# 02_Connectors.net
KiCad netlist of a schematic drawn in Altium Designer
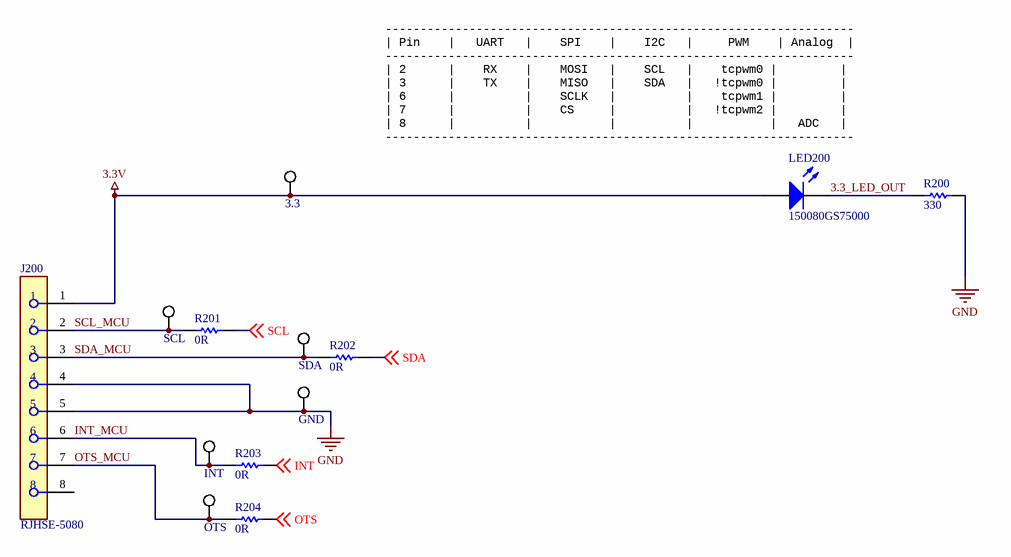
[diagram p0: 02_Connectors.SchDoc]

(export (version "E")
  (design (tool "Eeschema 10.0.6"))
  (components
    (comp (ref "3.3")
      (value "5019")
      (footprint "KSTN-5019_V")
      (description "Test Point, 1 Position SMD, RoHS, Tape and Reel")
      (fields (field (name "MANUFACTURER") "Keystone Electronics"))
      (libsource (lib "ECE453") (part "CMP-1672-00008-1"))
    )
    (comp (ref "GND")
      (value "5019")
      (footprint "KSTN-5019_V")
      (description "Test Point, 1 Position SMD, RoHS, Tape and Reel")
      (fields (field (name "MANUFACTURER") "Keystone Electronics"))
      (libsource (lib "ECE453") (part "CMP-1672-00008-1"))
    )
    (comp (ref "INT")
      (value "5019")
      (footprint "KSTN-5019_V")
      (description "Test Point, 1 Position SMD, RoHS, Tape and Reel")
      (fields (field (name "MANUFACTURER") "Keystone Electronics"))
      (libsource (lib "ECE453") (part "CMP-1672-00008-1"))
    )
    (comp (ref "J200")
      (value "RJHSE-5080")
      (footprint "FP-RJHSE-5080-MFG")
      (description "CONN MOD JACK 8P8C R/A UNSHLD")
      (fields
        (field (name "OCTOPART") "https://octopart.com/rjhse-5080-amphenol-45060")
        (field (name "MANUFACTURER") "Amphenol")
      )
      (libsource (lib "Altium Content Vault") (part "b0a0b555dd3abf3683e7c330df25cc4"))
    )
    (comp (ref "LED200")
      (value "150080GS75000")
      (footprint "0805_A")
      (description "SMD mono-color Chip LED, WL-SMCW, Green")
      (fields (field (name "MANUFACTURER") "Wuerth Elektronik"))
      (libsource (lib "ECE453") (part "CMP-1426-00007-1"))
    )
    (comp (ref "OTS")
      (value "5019")
      (footprint "KSTN-5019_V")
      (description "Test Point, 1 Position SMD, RoHS, Tape and Reel")
      (fields (field (name "MANUFACTURER") "Keystone Electronics"))
      (libsource (lib "ECE453") (part "CMP-1672-00008-1"))
    )
    (comp (ref "R200")
      (value "RC0805FR-07330RL")
      (footprint "RESC2013X60X35LL10T20")
      (description "Chip Resistor, 330 Ohm, +/- 1%, 125 mW, -55 to 155 degC, 0805 (2012 Metric), RoHS, Tape and Reel")
      (fields
        (field (name "MANUFACTURER") "Yageo")
        (field (name "TOLERANCE") "1%")
        (field (name "RESISTANCE") "330")
      )
      (libsource (lib "ECE453") (part "CMP-2000-06960-1"))
    )
    (comp (ref "R201")
      (value "0R")
      (footprint "RES_0805")
      (description "Chip Resistor, 0 Ohm, +/- 1%, 0.125 W, -55 to 155 degC, 0805 (2012 Metric), RoHS, Tape and Reel")
      (fields (field (name "PARTNUMBER") "ERJ-6GEY0R00V") (field (name "TOLERANCE") "5%"))
      (libsource (lib "ECE453") (part "CMP-1665-00002-5"))
    )
    (comp (ref "R202")
      (value "0R")
      (footprint "RESC2013X70X40NL20T20")
      (description "Chip Resistor, 0 Ohm, +/- 1%, 0.125 W, -55 to 155 degC, 0805 (2012 Metric), RoHS, Tape and Reel")
      (fields (field (name "PARTNUMBER") "ERJ-6GEY0R00V") (field (name "TOLERANCE") "5%"))
      (libsource (lib "ECE453") (part "CMP-1665-00002-5"))
    )
    (comp (ref "R203")
      (value "0R")
      (footprint "RESC2013X70X40NL20T20")
      (description "Chip Resistor, 0 Ohm, +/- 1%, 0.125 W, -55 to 155 degC, 0805 (2012 Metric), RoHS, Tape and Reel")
      (fields (field (name "PARTNUMBER") "ERJ-6GEY0R00V") (field (name "TOLERANCE") "5%"))
      (libsource (lib "ECE453") (part "CMP-1665-00002-5"))
    )
    (comp (ref "R204")
      (value "0R")
      (footprint "RESC2013X70X40NL20T20")
      (description "Chip Resistor, 0 Ohm, +/- 1%, 0.125 W, -55 to 155 degC, 0805 (2012 Metric), RoHS, Tape and Reel")
      (fields (field (name "PARTNUMBER") "ERJ-6GEY0R00V") (field (name "TOLERANCE") "5%"))
      (libsource (lib "ECE453") (part "CMP-1665-00002-5"))
    )
    (comp (ref "SCL")
      (value "5019")
      (footprint "KSTN-5019_V")
      (description "Test Point, 1 Position SMD, RoHS, Tape and Reel")
      (fields (field (name "MANUFACTURER") "Keystone Electronics"))
      (libsource (lib "ECE453") (part "CMP-1672-00008-1"))
    )
    (comp (ref "SDA")
      (value "5019")
      (footprint "KSTN-5019_V")
      (description "Test Point, 1 Position SMD, RoHS, Tape and Reel")
      (fields (field (name "MANUFACTURER") "Keystone Electronics"))
      (libsource (lib "ECE453") (part "CMP-1672-00008-1"))
    )
  )
  (nets
    (net (code "1") (name "/3.3_LED_OUT") (class "Default")
      (node (ref "LED200") (pin "1") (pinfunction "K_1") (pintype "passive"))
      (node (ref "R200") (pin "1") (pinfunction "1_1") (pintype "passive"))
    )
    (net (code "2") (name "/INT_MCU") (class "Default")
      (node (ref "INT") (pin "1") (pinfunction "1_1") (pintype "passive"))
      (node (ref "J200") (pin "6") (pinfunction "6_6") (pintype "passive"))
      (node (ref "R203") (pin "1") (pinfunction "1_1") (pintype "passive"))
    )
    (net (code "3") (name "/OTS_MCU") (class "Default")
      (node (ref "J200") (pin "7") (pinfunction "7_7") (pintype "passive"))
      (node (ref "OTS") (pin "1") (pinfunction "1_1") (pintype "passive"))
      (node (ref "R204") (pin "1") (pinfunction "1_1") (pintype "passive"))
    )
    (net (code "4") (name "/SCL_MCU") (class "Default")
      (node (ref "J200") (pin "2") (pinfunction "2_2") (pintype "passive"))
      (node (ref "R201") (pin "1") (pinfunction "1_1") (pintype "passive"))
      (node (ref "SCL") (pin "1") (pinfunction "1_1") (pintype "passive"))
    )
    (net (code "5") (name "/SDA_MCU") (class "Default")
      (node (ref "J200") (pin "3") (pinfunction "3_3") (pintype "passive"))
      (node (ref "R202") (pin "1") (pinfunction "1_1") (pintype "passive"))
      (node (ref "SDA") (pin "1") (pinfunction "1_1") (pintype "passive"))
    )
    (net (code "6") (name "3.3V") (class "Default")
      (node (ref "3.3") (pin "1") (pinfunction "1_1") (pintype "passive"))
      (node (ref "J200") (pin "1") (pinfunction "1_1") (pintype "passive"))
      (node (ref "LED200") (pin "2") (pinfunction "A_2") (pintype "passive"))
    )
    (net (code "7") (name "GND") (class "Default")
      (node (ref "GND") (pin "1") (pinfunction "1_1") (pintype "passive"))
      (node (ref "J200") (pin "4") (pinfunction "4_4") (pintype "passive"))
      (node (ref "J200") (pin "5") (pinfunction "5_5") (pintype "passive"))
      (node (ref "R200") (pin "2") (pinfunction "2_2") (pintype "passive"))
    )
    (net (code "8") (name "INT") (class "Default")
      (node (ref "R203") (pin "2") (pinfunction "2_2") (pintype "passive"))
    )
    (net (code "9") (name "OTS") (class "Default")
      (node (ref "R204") (pin "2") (pinfunction "2_2") (pintype "passive"))
    )
    (net (code "10") (name "SCL") (class "Default")
      (node (ref "R201") (pin "2") (pinfunction "2_2") (pintype "passive"))
    )
    (net (code "11") (name "SDA") (class "Default")
      (node (ref "R202") (pin "2") (pinfunction "2_2") (pintype "passive"))
    )
    (net (code "12") (name "unconnected-(J200-Pad8)") (class "Default")
      (node (ref "J200") (pin "8") (pinfunction "8_8") (pintype "passive"))
    )
  )
)
